# 11_MIPI_CAM_RX.net
KiCad netlist of a schematic drawn in Altium Designer
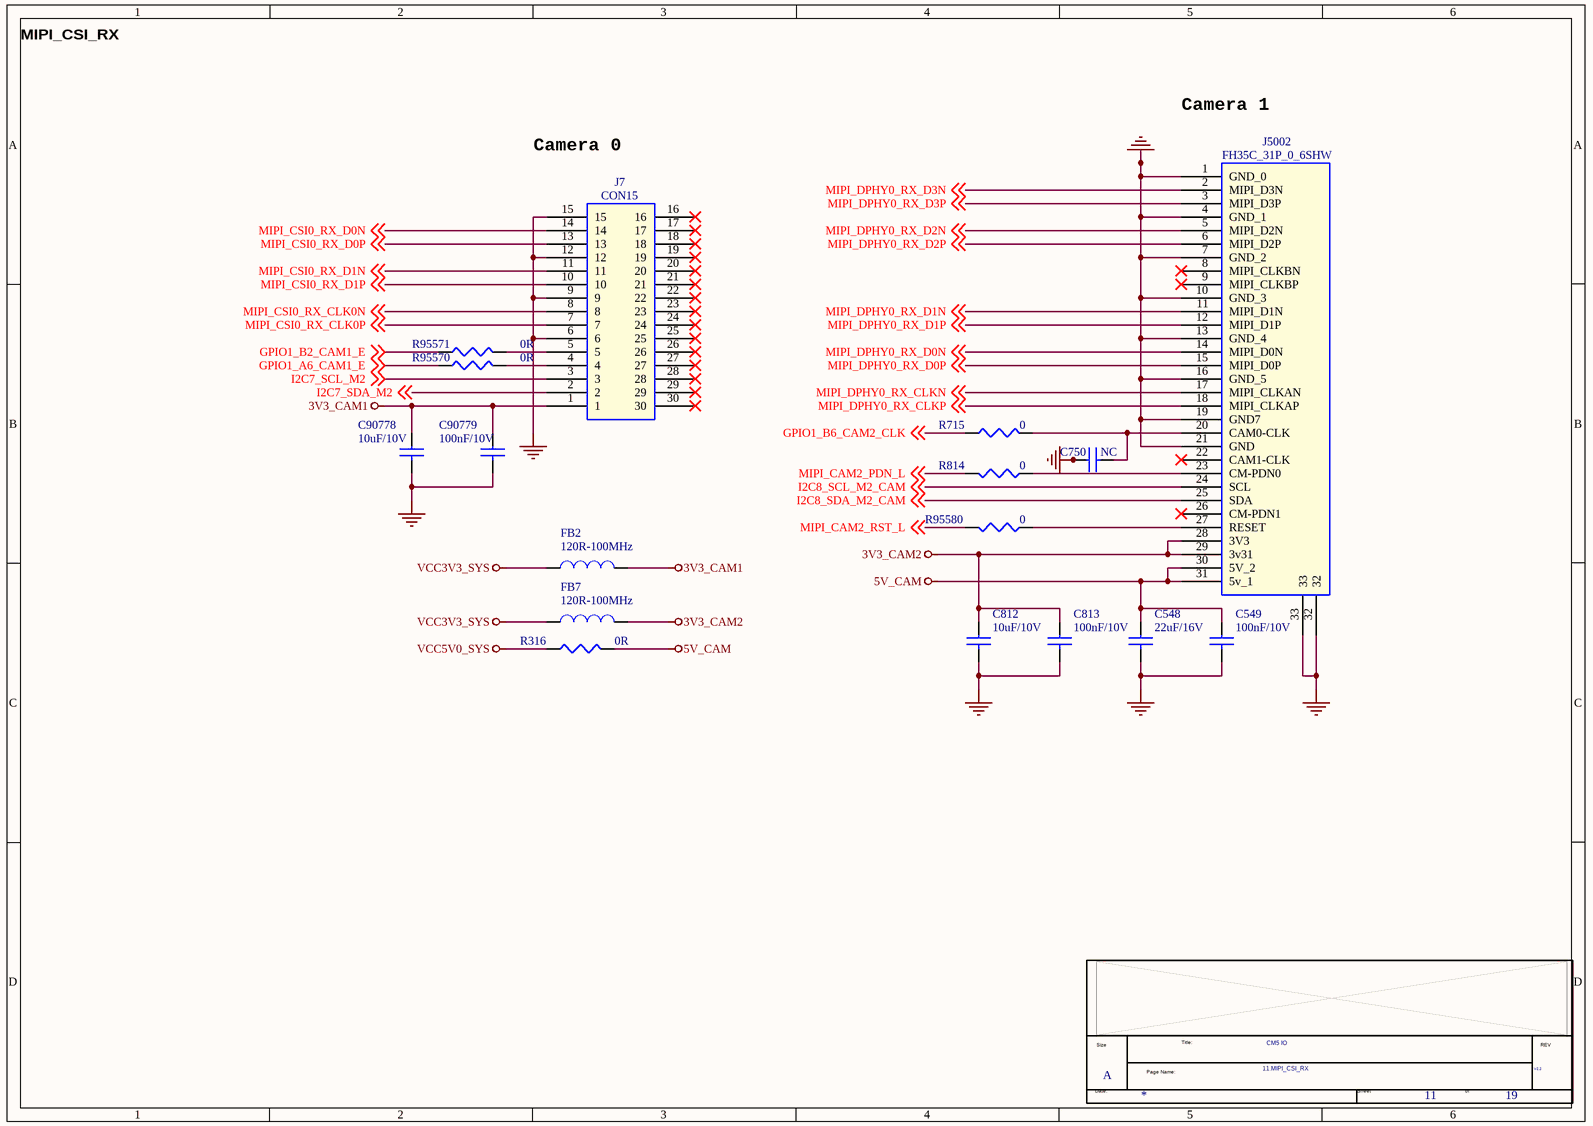
[diagram p0: 11_MIPI_CAM_RX.SchDoc]

(export (version "E")
  (design (tool "Eeschema 10.0.6"))
  (components
    (comp (ref "*")
      (value "radxa_1010")
      (fields
        (field (name "DOC") "11.MIPI_CSI_RX")
        (field (name "REVCODE") "V2.2")
        (field (name "TITLE") "CM5 IO")
        (field (name "PAGE SIZE") "A")
        (field (name "PAGE NUMBER") "11")
        (field (name "PAGE COUNT") "19")
      )
      (libsource (lib "*") (part "radxa_1010"))
    )
    (comp (ref "C548")
      (value "22uF/16V")
      (footprint "C0603")
      (description "cap,10.00uF,+/-10%,10V,X5R,C0603")
      (fields
        (field (name "VOLTAGE") "10V")
        (field (name "MANUFACTURER") "TDK")
        (field (name "CREATED BY") "JJJ")
      )
      (libsource (lib "*") (part "CAP NP_0_Dup2"))
    )
    (comp (ref "C549")
      (value "100nF/10V")
      (footprint "C0201")
      (description "cap,100.00nF,+/-10%,16V,X5R,C0402")
      (fields
        (field (name "VOLTAGE") "16V")
        (field (name "TOLERANCE") "10%")
        (field (name "CREATED BY") "JJJ")
      )
      (libsource (lib "*") (part "CAP NP_0_Dup2"))
    )
    (comp (ref "C750")
      (value "NC")
      (footprint "C0201")
      (description "0201 ∮ 10% 100nf X5R 6.3V")
      (libsource (lib "*") (part "C / 100 / nF / 0201_3"))
    )
    (comp (ref "C812")
      (value "10uF/10V")
      (footprint "C0603")
      (description "cap,10.00uF,+/-10%,10V,X5R,C0603")
      (fields
        (field (name "VOLTAGE") "10V")
        (field (name "MANUFACTURER") "TDK")
        (field (name "CREATED BY") "JJJ")
      )
      (libsource (lib "*") (part "CAP NP_0_Dup2"))
    )
    (comp (ref "C813")
      (value "100nF/10V")
      (footprint "C0201")
      (description "cap,100.00nF,+/-10%,16V,X5R,C0402")
      (fields
        (field (name "VOLTAGE") "16V")
        (field (name "TOLERANCE") "10%")
        (field (name "CREATED BY") "JJJ")
      )
      (libsource (lib "*") (part "CAP NP_0_Dup2"))
    )
    (comp (ref "C90778")
      (value "10uF/10V")
      (footprint "C0603")
      (description "cap,10.00uF,+/-10%,10V,X5R,C0603")
      (fields
        (field (name "VOLTAGE") "10V")
        (field (name "MANUFACTURER") "TDK")
        (field (name "CREATED BY") "JJJ")
      )
      (libsource (lib "*") (part "CAP NP_0_Dup2"))
    )
    (comp (ref "C90779")
      (value "100nF/10V")
      (footprint "C0201")
      (description "cap,100.00nF,+/-10%,16V,X5R,C0402")
      (fields
        (field (name "VOLTAGE") "16V")
        (field (name "TOLERANCE") "10%")
        (field (name "CREATED BY") "JJJ")
      )
      (libsource (lib "*") (part "CAP NP_0_Dup2"))
    )
    (comp (ref "FB2")
      (value "120R-100MHz")
      (footprint "L0402")
      (description "BEAD,120R@100MHz,current=2000mA,0603")
      (fields
        (field (name "TOLERANCE") "25%")
        (field (name "MANUFACTURER") "Murata")
        (field (name "CREATED BY") "DZS")
      )
      (libsource (lib "*") (part "BEAD_1"))
    )
    (comp (ref "FB7")
      (value "120R-100MHz")
      (footprint "L0402")
      (description "BEAD,120R@100MHz,current=2000mA,0603")
      (fields
        (field (name "TOLERANCE") "25%")
        (field (name "MANUFACTURER") "Murata")
        (field (name "CREATED BY") "DZS")
      )
      (libsource (lib "*") (part "BEAD_1"))
    )
    (comp (ref "J7") (value "CON15") (footprint "FPC15PIN-1.0MM-LS") (libsource (lib "*") (part "CON15_5")))
    (comp (ref "J5002")
      (value "FH35C_31P_0_6SHW")
      (footprint "FH35C_31P_0_6SHW")
      (fields (field (name "CREATED BY") "JJJ"))
      (libsource (lib "*") (part "DCDC_SY8113_4"))
    )
    (comp (ref "R316")
      (value "0R")
      (footprint "R0402")
      (description "通用厚膜电阻,0R,+/-5%,R0805,1/8W.")
      (fields
        (field (name "TOLERANCE") "5%")
        (field (name "MANUFACTURER") "YAGEO")
        (field (name "CREATED BY") "YTL")
      )
      (libsource (lib "*") (part "RESISTOR_1_Dup1"))
    )
    (comp (ref "R715") (value "0") (footprint "R0603") (libsource (lib "*") (part "R0402_0")))
    (comp (ref "R814")
      (value "0")
      (footprint "R0201")
      (description "0201 ∮5% 0ohm 1/20W")
      (fields (field (name "PART_NUMBER") "R31-0201J0R00F0000"))
      (libsource (lib "*") (part "R / 0 / ohm / 0201_0"))
    )
    (comp (ref "R95570")
      (value "0R")
      (footprint "R0402")
      (description "通用厚膜电阻,0R,+/-5%,R0805,1/8W.")
      (fields
        (field (name "TOLERANCE") "5%")
        (field (name "MANUFACTURER") "YAGEO")
        (field (name "CREATED BY") "YTL")
      )
      (libsource (lib "*") (part "RESISTOR_1_Dup1"))
    )
    (comp (ref "R95571")
      (value "0R")
      (footprint "R0402")
      (description "通用厚膜电阻,0R,+/-5%,R0805,1/8W.")
      (fields
        (field (name "TOLERANCE") "5%")
        (field (name "MANUFACTURER") "YAGEO")
        (field (name "CREATED BY") "YTL")
      )
      (libsource (lib "*") (part "RESISTOR_1_Dup1"))
    )
    (comp (ref "R95580")
      (value "0")
      (footprint "R0201")
      (description "0201 ∮5% 0ohm 1/20W")
      (fields (field (name "PART_NUMBER") "R31-0201J0R00F0000"))
      (libsource (lib "*") (part "R / 0 / ohm / 0201_0"))
    )
  )
  (nets
    (net (code "1") (name "3V3_CAM1") (class "Default")
      (node (ref "C90778") (pin "1") (pinfunction "1_1") (pintype "passive"))
      (node (ref "C90779") (pin "1") (pinfunction "1_1") (pintype "passive"))
      (node (ref "FB2") (pin "2") (pinfunction "2_2") (pintype "passive"))
      (node (ref "J7") (pin "1") (pinfunction "1_1") (pintype "passive"))
    )
    (net (code "2") (name "3V3_CAM2") (class "Default")
      (node (ref "C812") (pin "1") (pinfunction "1_1") (pintype "passive"))
      (node (ref "C813") (pin "1") (pinfunction "1_1") (pintype "passive"))
      (node (ref "FB7") (pin "2") (pinfunction "2_2") (pintype "passive"))
      (node (ref "J5002") (pin "28") (pinfunction "3V3_28") (pintype "passive"))
      (node (ref "J5002") (pin "29") (pinfunction "3v31_29") (pintype "passive"))
    )
    (net (code "3") (name "5V_CAM") (class "Default")
      (node (ref "C548") (pin "1") (pinfunction "1_1") (pintype "passive"))
      (node (ref "C549") (pin "1") (pinfunction "1_1") (pintype "passive"))
      (node (ref "J5002") (pin "30") (pinfunction "5V_2_30") (pintype "passive"))
      (node (ref "J5002") (pin "31") (pinfunction "5v_1_31") (pintype "passive"))
      (node (ref "R316") (pin "2") (pinfunction "2_2") (pintype "passive"))
    )
    (net (code "4") (name "GND") (class "Default")
      (node (ref "C548") (pin "2") (pinfunction "2_2") (pintype "passive"))
      (node (ref "C549") (pin "2") (pinfunction "2_2") (pintype "passive"))
      (node (ref "C750") (pin "1") (pinfunction "1_1") (pintype "passive"))
      (node (ref "C812") (pin "2") (pinfunction "2_2") (pintype "passive"))
      (node (ref "C813") (pin "2") (pinfunction "2_2") (pintype "passive"))
      (node (ref "C90778") (pin "2") (pinfunction "2_2") (pintype "passive"))
      (node (ref "C90779") (pin "2") (pinfunction "2_2") (pintype "passive"))
      (node (ref "J5002") (pin "1") (pinfunction "GND_0_1") (pintype "passive"))
      (node (ref "J5002") (pin "10") (pinfunction "GND_3_10") (pintype "passive"))
      (node (ref "J5002") (pin "13") (pinfunction "GND_4_13") (pintype "passive"))
      (node (ref "J5002") (pin "16") (pinfunction "GND_5_16") (pintype "passive"))
      (node (ref "J5002") (pin "19") (pinfunction "GND7_19") (pintype "passive"))
      (node (ref "J5002") (pin "21") (pinfunction "GND_21") (pintype "passive"))
      (node (ref "J5002") (pin "32") (pinfunction "32_32") (pintype "passive"))
      (node (ref "J5002") (pin "33") (pinfunction "33_33") (pintype "passive"))
      (node (ref "J5002") (pin "4") (pinfunction "GND_1_4") (pintype "passive"))
      (node (ref "J5002") (pin "7") (pinfunction "GND_2_7") (pintype "passive"))
      (node (ref "J7") (pin "12") (pinfunction "12_12") (pintype "passive"))
      (node (ref "J7") (pin "15") (pinfunction "15_15") (pintype "passive"))
      (node (ref "J7") (pin "6") (pinfunction "6_6") (pintype "passive"))
      (node (ref "J7") (pin "9") (pinfunction "9_9") (pintype "passive"))
    )
    (net (code "5") (name "GPIO1_A6_CAM1_E") (class "Default")
      (node (ref "R95570") (pin "1") (pinfunction "1_1") (pintype "passive"))
    )
    (net (code "6") (name "GPIO1_B2_CAM1_E") (class "Default")
      (node (ref "R95571") (pin "1") (pinfunction "1_1") (pintype "passive"))
    )
    (net (code "7") (name "GPIO1_B6_CAM2_CLK") (class "Default")
      (node (ref "R715") (pin "1") (pinfunction "1_1") (pintype "passive"))
    )
    (net (code "8") (name "I2C7_SCL_M2") (class "Default")
      (node (ref "J7") (pin "3") (pinfunction "3_3") (pintype "passive"))
    )
    (net (code "9") (name "I2C7_SDA_M2") (class "Default")
      (node (ref "J7") (pin "2") (pinfunction "2_2") (pintype "passive"))
    )
    (net (code "10") (name "I2C8_SCL_M2_CAM") (class "Default")
      (node (ref "J5002") (pin "24") (pinfunction "SCL_24") (pintype "passive"))
    )
    (net (code "11") (name "I2C8_SDA_M2_CAM") (class "Default")
      (node (ref "J5002") (pin "25") (pinfunction "SDA_25") (pintype "passive"))
    )
    (net (code "12") (name "MIPI_CAM2_PDN_L") (class "Default")
      (node (ref "R814") (pin "1") (pinfunction "1_1") (pintype "passive"))
    )
    (net (code "13") (name "MIPI_CAM2_RST_L") (class "Default")
      (node (ref "R95580") (pin "1") (pinfunction "1_1") (pintype "passive"))
    )
    (net (code "14") (name "MIPI_CSI0_RX_CLK0N") (class "Default")
      (node (ref "J7") (pin "8") (pinfunction "8_8") (pintype "passive"))
    )
    (net (code "15") (name "MIPI_CSI0_RX_CLK0P") (class "Default")
      (node (ref "J7") (pin "7") (pinfunction "7_7") (pintype "passive"))
    )
    (net (code "16") (name "MIPI_CSI0_RX_D0N") (class "Default")
      (node (ref "J7") (pin "14") (pinfunction "14_14") (pintype "passive"))
    )
    (net (code "17") (name "MIPI_CSI0_RX_D0P") (class "Default")
      (node (ref "J7") (pin "13") (pinfunction "13_13") (pintype "passive"))
    )
    (net (code "18") (name "MIPI_CSI0_RX_D1N") (class "Default")
      (node (ref "J7") (pin "11") (pinfunction "11_11") (pintype "passive"))
    )
    (net (code "19") (name "MIPI_CSI0_RX_D1P") (class "Default")
      (node (ref "J7") (pin "10") (pinfunction "10_10") (pintype "passive"))
    )
    (net (code "20") (name "MIPI_DPHY0_RX_CLKN") (class "Default")
      (node (ref "J5002") (pin "17") (pinfunction "MIPI_CLKAN_17") (pintype "passive"))
    )
    (net (code "21") (name "MIPI_DPHY0_RX_CLKP") (class "Default")
      (node (ref "J5002") (pin "18") (pinfunction "MIPI_CLKAP_18") (pintype "passive"))
    )
    (net (code "22") (name "MIPI_DPHY0_RX_D0N") (class "Default")
      (node (ref "J5002") (pin "14") (pinfunction "MIPI_D0N_14") (pintype "passive"))
    )
    (net (code "23") (name "MIPI_DPHY0_RX_D0P") (class "Default")
      (node (ref "J5002") (pin "15") (pinfunction "MIPI_D0P_15") (pintype "passive"))
    )
    (net (code "24") (name "MIPI_DPHY0_RX_D1N") (class "Default")
      (node (ref "J5002") (pin "11") (pinfunction "MIPI_D1N_11") (pintype "passive"))
    )
    (net (code "25") (name "MIPI_DPHY0_RX_D1P") (class "Default")
      (node (ref "J5002") (pin "12") (pinfunction "MIPI_D1P_12") (pintype "passive"))
    )
    (net (code "26") (name "MIPI_DPHY0_RX_D2N") (class "Default")
      (node (ref "J5002") (pin "5") (pinfunction "MIPI_D2N_5") (pintype "passive"))
    )
    (net (code "27") (name "MIPI_DPHY0_RX_D2P") (class "Default")
      (node (ref "J5002") (pin "6") (pinfunction "MIPI_D2P_6") (pintype "passive"))
    )
    (net (code "28") (name "MIPI_DPHY0_RX_D3N") (class "Default")
      (node (ref "J5002") (pin "2") (pinfunction "MIPI_D3N_2") (pintype "passive"))
    )
    (net (code "29") (name "MIPI_DPHY0_RX_D3P") (class "Default")
      (node (ref "J5002") (pin "3") (pinfunction "MIPI_D3P_3") (pintype "passive"))
    )
    (net (code "30") (name "Net-(J7-Pad4)") (class "Default")
      (node (ref "J7") (pin "4") (pinfunction "4_4") (pintype "passive"))
      (node (ref "R95570") (pin "2") (pinfunction "2_2") (pintype "passive"))
    )
    (net (code "31") (name "Net-(J7-Pad5)") (class "Default")
      (node (ref "J7") (pin "5") (pinfunction "5_5") (pintype "passive"))
      (node (ref "R95571") (pin "2") (pinfunction "2_2") (pintype "passive"))
    )
    (net (code "32") (name "Net-(J5002-CAM0-CLK)") (class "Default")
      (node (ref "C750") (pin "2") (pinfunction "2_2") (pintype "passive"))
      (node (ref "J5002") (pin "20") (pinfunction "CAM0-CLK_20") (pintype "passive"))
      (node (ref "R715") (pin "2") (pinfunction "2_2") (pintype "passive"))
    )
    (net (code "33") (name "Net-(J5002-CM-PDN0)") (class "Default")
      (node (ref "J5002") (pin "23") (pinfunction "CM-PDN0_23") (pintype "passive"))
      (node (ref "R814") (pin "2") (pinfunction "2_2") (pintype "passive"))
    )
    (net (code "34") (name "Net-(J5002-RESET)") (class "Default")
      (node (ref "J5002") (pin "27") (pinfunction "RESET_27") (pintype "passive"))
      (node (ref "R95580") (pin "2") (pinfunction "2_2") (pintype "passive"))
    )
    (net (code "35") (name "VCC3V3_SYS") (class "Default")
      (node (ref "FB2") (pin "1") (pinfunction "1_1") (pintype "passive"))
      (node (ref "FB7") (pin "1") (pinfunction "1_1") (pintype "passive"))
    )
    (net (code "36") (name "VCC5V0_SYS") (class "Default")
      (node (ref "R316") (pin "1") (pinfunction "1_1") (pintype "passive"))
    )
    (net (code "37") (name "unconnected-(J7-Pad16)") (class "Default")
      (node (ref "J7") (pin "16") (pinfunction "16_16") (pintype "passive+no_connect"))
    )
    (net (code "38") (name "unconnected-(J7-Pad17)") (class "Default")
      (node (ref "J7") (pin "17") (pinfunction "17_17") (pintype "passive+no_connect"))
    )
    (net (code "39") (name "unconnected-(J7-Pad18)") (class "Default")
      (node (ref "J7") (pin "18") (pinfunction "18_18") (pintype "passive+no_connect"))
    )
    (net (code "40") (name "unconnected-(J7-Pad19)") (class "Default")
      (node (ref "J7") (pin "19") (pinfunction "19_19") (pintype "passive+no_connect"))
    )
    (net (code "41") (name "unconnected-(J7-Pad20)") (class "Default")
      (node (ref "J7") (pin "20") (pinfunction "20_20") (pintype "passive+no_connect"))
    )
    (net (code "42") (name "unconnected-(J7-Pad21)") (class "Default")
      (node (ref "J7") (pin "21") (pinfunction "21_21") (pintype "passive+no_connect"))
    )
    (net (code "43") (name "unconnected-(J7-Pad22)") (class "Default")
      (node (ref "J7") (pin "22") (pinfunction "22_22") (pintype "passive+no_connect"))
    )
    (net (code "44") (name "unconnected-(J7-Pad23)") (class "Default")
      (node (ref "J7") (pin "23") (pinfunction "23_23") (pintype "passive+no_connect"))
    )
    (net (code "45") (name "unconnected-(J7-Pad24)") (class "Default")
      (node (ref "J7") (pin "24") (pinfunction "24_24") (pintype "passive+no_connect"))
    )
    (net (code "46") (name "unconnected-(J7-Pad25)") (class "Default")
      (node (ref "J7") (pin "25") (pinfunction "25_25") (pintype "passive+no_connect"))
    )
    (net (code "47") (name "unconnected-(J7-Pad26)") (class "Default")
      (node (ref "J7") (pin "26") (pinfunction "26_26") (pintype "passive+no_connect"))
    )
    (net (code "48") (name "unconnected-(J7-Pad27)") (class "Default")
      (node (ref "J7") (pin "27") (pinfunction "27_27") (pintype "passive+no_connect"))
    )
    (net (code "49") (name "unconnected-(J7-Pad28)") (class "Default")
      (node (ref "J7") (pin "28") (pinfunction "28_28") (pintype "passive+no_connect"))
    )
    (net (code "50") (name "unconnected-(J7-Pad29)") (class "Default")
      (node (ref "J7") (pin "29") (pinfunction "29_29") (pintype "passive+no_connect"))
    )
    (net (code "51") (name "unconnected-(J7-Pad30)") (class "Default")
      (node (ref "J7") (pin "30") (pinfunction "30_30") (pintype "passive+no_connect"))
    )
    (net (code "52") (name "unconnected-(J5002-CAM1-CLK-Pad22)") (class "Default")
      (node (ref "J5002") (pin "22") (pinfunction "CAM1-CLK_22") (pintype "passive+no_connect"))
    )
    (net (code "53") (name "unconnected-(J5002-CM-PDN1-Pad26)") (class "Default")
      (node (ref "J5002") (pin "26") (pinfunction "CM-PDN1_26") (pintype "passive+no_connect"))
    )
    (net (code "54") (name "unconnected-(J5002-MIPI_CLKBN-Pad8)") (class "Default")
      (node (ref "J5002") (pin "8") (pinfunction "MIPI_CLKBN_8") (pintype "passive+no_connect"))
    )
    (net (code "55") (name "unconnected-(J5002-MIPI_CLKBP-Pad9)") (class "Default")
      (node (ref "J5002") (pin "9") (pinfunction "MIPI_CLKBP_9") (pintype "passive+no_connect"))
    )
  )
)
